# Nusbio_smd.net
KiCad netlist of a schematic drawn in EAGLE
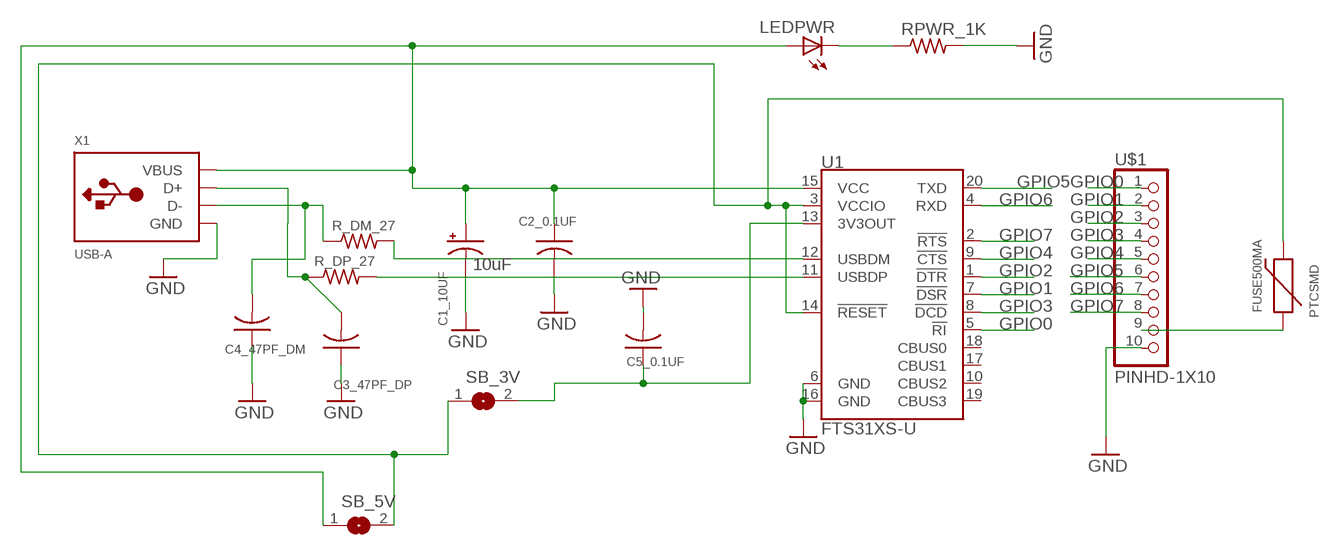
[diagram p0: schematic, sheet 1]

(export (version "E")
  (design (tool "Eeschema 10.0.6"))
  (components
    (comp (ref "C1_10UF")
      (value "10uF")
      (footprint "eagle-import:EIA3216")
      (libsource (lib "eagle-import") (part "10UF-16V-10%(TANT)"))
    )
    (comp (ref "C2_0.1UF")
      (value "C-USC1206")
      (footprint "eagle-import:C1206")
      (libsource (lib "eagle-import") (part "C-USC1206"))
    )
    (comp (ref "C3_47PF_DP")
      (value "C-USC1206")
      (footprint "eagle-import:C1206")
      (libsource (lib "eagle-import") (part "C-USC1206"))
    )
    (comp (ref "C4_47PF_DM")
      (value "C-USC1206")
      (footprint "eagle-import:C1206")
      (libsource (lib "eagle-import") (part "C-USC1206"))
    )
    (comp (ref "C5_0.1UF")
      (value "C-USC1206")
      (footprint "eagle-import:C1206")
      (libsource (lib "eagle-import") (part "C-USC1206"))
    )
    (comp (ref "FUSE500MA")
      (value "PTCSMD")
      (footprint "eagle-import:PTC-1206")
      (libsource (lib "eagle-import") (part "PTCSMD"))
    )
    (comp (ref "LEDPWR")
      (value "LEDCHIPLED_0805")
      (footprint "eagle-import:CHIPLED_0805")
      (libsource (lib "eagle-import") (part "LEDCHIPLED_0805"))
    )
    (comp (ref "RPWR_1K")
      (value "R-US_R0805")
      (footprint "eagle-import:R0805")
      (libsource (lib "eagle-import") (part "R-US_R0805"))
    )
    (comp (ref "R_DM_27")
      (value "R-US_R0805")
      (footprint "eagle-import:R0805")
      (libsource (lib "eagle-import") (part "R-US_R0805"))
    )
    (comp (ref "R_DP_27")
      (value "R-US_R0805")
      (footprint "eagle-import:R0805")
      (libsource (lib "eagle-import") (part "R-US_R0805"))
    )
    (comp (ref "SB_3V")
      (value "SOLDERJUMPERREFLOW")
      (footprint "eagle-import:SOLDERJUMPER_REFLOW")
      (libsource (lib "eagle-import") (part "SOLDERJUMPERREFLOW"))
    )
    (comp (ref "SB_5V")
      (value "SOLDERJUMPERREFLOW")
      (footprint "eagle-import:SOLDERJUMPER_REFLOW")
      (libsource (lib "eagle-import") (part "SOLDERJUMPERREFLOW"))
    )
    (comp (ref "U$1")
      (value "PINHD-1X10")
      (footprint "eagle-import:1X10-BIG")
      (libsource (lib "eagle-import") (part "PINHD-1X10"))
    )
    (comp (ref "U1")
      (value "FTS31XS-U")
      (footprint "eagle-import:SSOP20_L")
      (libsource (lib "eagle-import") (part "FT231XS"))
    )
    (comp (ref "X1")
      (value "USB-A")
      (footprint "eagle-import:MOLEX_480371000")
      (libsource (lib "eagle-import") (part "USB-A"))
    )
  )
  (nets
    (net (code "1") (name "/GPIO0") (class "Default")
      (node (ref "U$1") (pin "1") (pinfunction "1_1") (pintype "passive"))
      (node (ref "U1") (pin "5") (pinfunction "~{RI}_5") (pintype "bidirectional"))
    )
    (net (code "2") (name "/GPIO1") (class "Default")
      (node (ref "U$1") (pin "2") (pinfunction "2_2") (pintype "passive"))
      (node (ref "U1") (pin "7") (pinfunction "~{DSR}_7") (pintype "bidirectional"))
    )
    (net (code "3") (name "/GPIO2") (class "Default")
      (node (ref "U$1") (pin "3") (pinfunction "3_3") (pintype "passive"))
      (node (ref "U1") (pin "1") (pinfunction "~{DTR}_1") (pintype "bidirectional"))
    )
    (net (code "4") (name "/GPIO3") (class "Default")
      (node (ref "U$1") (pin "4") (pinfunction "4_4") (pintype "passive"))
      (node (ref "U1") (pin "8") (pinfunction "~{DCD}_8") (pintype "bidirectional"))
    )
    (net (code "5") (name "/GPIO4") (class "Default")
      (node (ref "U$1") (pin "5") (pinfunction "5_5") (pintype "passive"))
      (node (ref "U1") (pin "9") (pinfunction "~{CTS}_9") (pintype "bidirectional"))
    )
    (net (code "6") (name "/GPIO5") (class "Default")
      (node (ref "U$1") (pin "6") (pinfunction "6_6") (pintype "passive"))
      (node (ref "U1") (pin "20") (pinfunction "TXD_20") (pintype "bidirectional"))
    )
    (net (code "7") (name "/GPIO6") (class "Default")
      (node (ref "U$1") (pin "7") (pinfunction "7_7") (pintype "passive"))
      (node (ref "U1") (pin "4") (pinfunction "RXD_4") (pintype "bidirectional"))
    )
    (net (code "8") (name "/GPIO7") (class "Default")
      (node (ref "U$1") (pin "8") (pinfunction "8_8") (pintype "passive"))
      (node (ref "U1") (pin "2") (pinfunction "~{RTS}_2") (pintype "bidirectional"))
    )
    (net (code "9") (name "GND") (class "Default")
      (node (ref "C1_10UF") (pin "C") (pinfunction "-_C") (pintype "passive"))
      (node (ref "C2_0.1UF") (pin "2") (pinfunction "2_2") (pintype "passive"))
      (node (ref "C3_47PF_DP") (pin "1") (pinfunction "1_1") (pintype "passive"))
      (node (ref "C4_47PF_DM") (pin "1") (pinfunction "1_1") (pintype "passive"))
      (node (ref "C5_0.1UF") (pin "2") (pinfunction "2_2") (pintype "passive"))
      (node (ref "RPWR_1K") (pin "2") (pinfunction "2_2") (pintype "passive"))
      (node (ref "U$1") (pin "10") (pinfunction "10_10") (pintype "passive"))
      (node (ref "U1") (pin "16") (pinfunction "GND_16") (pintype "bidirectional"))
      (node (ref "U1") (pin "6") (pinfunction "GND_6") (pintype "bidirectional"))
      (node (ref "X1") (pin "4") (pinfunction "GND_4") (pintype "power_in"))
    )
    (net (code "10") (name "Net-(C1_10UF-+)") (class "Default")
      (node (ref "C1_10UF") (pin "A") (pinfunction "+_A") (pintype "passive"))
      (node (ref "C2_0.1UF") (pin "1") (pinfunction "1_1") (pintype "passive"))
      (node (ref "LEDPWR") (pin "A") (pinfunction "A_A") (pintype "passive"))
      (node (ref "SB_5V") (pin "1") (pinfunction "1_1") (pintype "passive"))
      (node (ref "U1") (pin "15") (pinfunction "VCC_15") (pintype "bidirectional"))
      (node (ref "X1") (pin "1") (pinfunction "VBUS_1") (pintype "power_in"))
    )
    (net (code "11") (name "Net-(FUSE500MA-Pad1)") (class "Default")
      (node (ref "FUSE500MA") (pin "1") (pinfunction "1_1") (pintype "bidirectional"))
      (node (ref "U$1") (pin "9") (pinfunction "9_9") (pintype "passive"))
    )
    (net (code "12") (name "Net-(LEDPWR-PadC)") (class "Default")
      (node (ref "LEDPWR") (pin "C") (pinfunction "C_C") (pintype "passive"))
      (node (ref "RPWR_1K") (pin "1") (pinfunction "1_1") (pintype "passive"))
    )
    (net (code "13") (name "Net-(U1-3V3OUT)") (class "Default")
      (node (ref "C5_0.1UF") (pin "1") (pinfunction "1_1") (pintype "passive"))
      (node (ref "SB_3V") (pin "2") (pinfunction "2_2") (pintype "passive"))
      (node (ref "U1") (pin "13") (pinfunction "3V3OUT_13") (pintype "bidirectional"))
    )
    (net (code "14") (name "Net-(U1-USBDM)") (class "Default")
      (node (ref "R_DM_27") (pin "2") (pinfunction "2_2") (pintype "passive"))
      (node (ref "U1") (pin "12") (pinfunction "USBDM_12") (pintype "bidirectional"))
    )
    (net (code "15") (name "Net-(U1-USBDP)") (class "Default")
      (node (ref "R_DP_27") (pin "2") (pinfunction "2_2") (pintype "passive"))
      (node (ref "U1") (pin "11") (pinfunction "USBDP_11") (pintype "bidirectional"))
    )
    (net (code "16") (name "Net-(U1-VCCIO)") (class "Default")
      (node (ref "FUSE500MA") (pin "2") (pinfunction "2_2") (pintype "bidirectional"))
      (node (ref "SB_3V") (pin "1") (pinfunction "1_1") (pintype "passive"))
      (node (ref "SB_5V") (pin "2") (pinfunction "2_2") (pintype "passive"))
      (node (ref "U1") (pin "14") (pinfunction "~{RESET}_14") (pintype "bidirectional"))
      (node (ref "U1") (pin "3") (pinfunction "VCCIO_3") (pintype "bidirectional"))
    )
    (net (code "17") (name "Net-(X1-D+)") (class "Default")
      (node (ref "C3_47PF_DP") (pin "2") (pinfunction "2_2") (pintype "passive"))
      (node (ref "R_DP_27") (pin "1") (pinfunction "1_1") (pintype "passive"))
      (node (ref "X1") (pin "3") (pinfunction "D+_3") (pintype "bidirectional"))
    )
    (net (code "18") (name "Net-(X1-D-)") (class "Default")
      (node (ref "C4_47PF_DM") (pin "2") (pinfunction "2_2") (pintype "passive"))
      (node (ref "R_DM_27") (pin "1") (pinfunction "1_1") (pintype "passive"))
      (node (ref "X1") (pin "2") (pinfunction "D-_2") (pintype "bidirectional"))
    )
    (net (code "19") (name "unconnected-(U1-CBUS0-Pad18)") (class "Default")
      (node (ref "U1") (pin "18") (pinfunction "CBUS0_18") (pintype "bidirectional"))
    )
    (net (code "20") (name "unconnected-(U1-CBUS1-Pad17)") (class "Default")
      (node (ref "U1") (pin "17") (pinfunction "CBUS1_17") (pintype "bidirectional"))
    )
    (net (code "21") (name "unconnected-(U1-CBUS2-Pad10)") (class "Default")
      (node (ref "U1") (pin "10") (pinfunction "CBUS2_10") (pintype "bidirectional"))
    )
    (net (code "22") (name "unconnected-(U1-CBUS3-Pad19)") (class "Default")
      (node (ref "U1") (pin "19") (pinfunction "CBUS3_19") (pintype "bidirectional"))
    )
  )
)
